# connector2.net
KiCad netlist of a schematic drawn in EAGLE
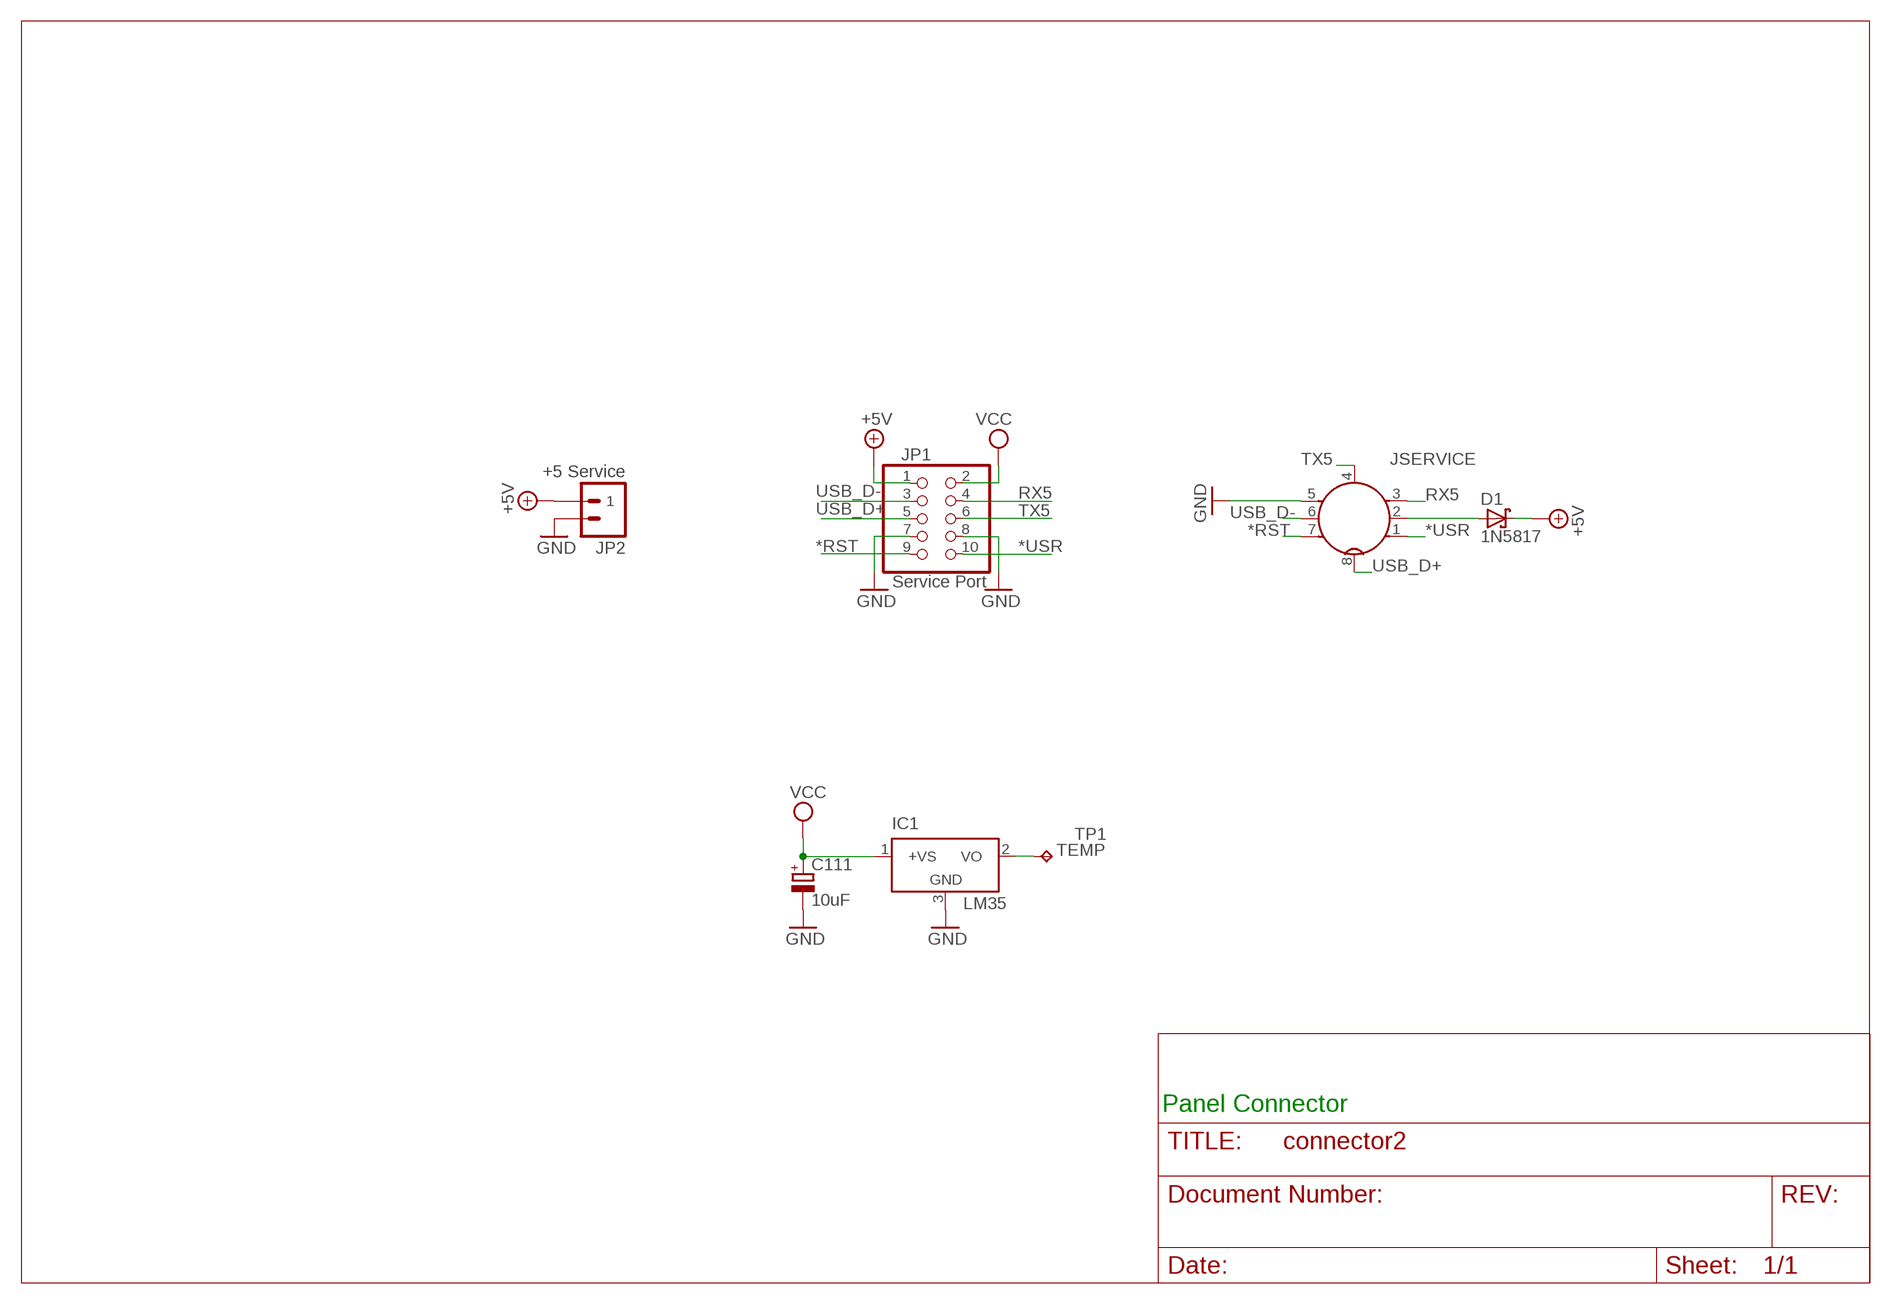
[diagram p0: schematic, sheet 1]

(export (version "E")
  (design (tool "Eeschema 10.0.6"))
  (components
    (comp (ref "C111")
      (value "10uF")
      (footprint "eagle-import:E2,5-6E")
      (libsource (lib "eagle-import") (part "CPOL-EUE2,5-6E"))
    )
    (comp (ref "D1")
      (value "1N5817")
      (footprint "eagle-import:DO41-150V")
      (libsource (lib "eagle-import") (part "1N5819-V"))
    )
    (comp (ref "IC1")
      (value "LM35")
      (footprint "eagle-import:TO92-50")
      (libsource (lib "eagle-import") (part "LM35"))
    )
    (comp (ref "JP1")
      (value "Service Port")
      (footprint "eagle-import:2X05")
      (libsource (lib "eagle-import") (part "HEADER-2X5"))
    )
    (comp (ref "JP2")
      (value "+5 Service")
      (footprint "eagle-import:MOLEX-1X2")
      (libsource (lib "eagle-import") (part "M02POLAR"))
    )
    (comp (ref "JSERVICE")
      (value "MIC_CONN_MALE_8P")
      (footprint "eagle-import:MIC_CONN_MALE_8P")
      (libsource (lib "eagle-import") (part "MIC_CONN_MALE_8P"))
    )
    (comp (ref "TP1")
      (value "TPPAD1-13")
      (footprint "eagle-import:P1-13")
      (fields (field (name "TP_SIGNAL_NAME") "TEMP"))
      (libsource (lib "eagle-import") (part "TPPAD1-13"))
    )
  )
  (nets
    (net (code "1") (name "+5V") (class "Default")
      (node (ref "D1") (pin "C") (pinfunction "C_C") (pintype "passive"))
      (node (ref "JP1") (pin "1") (pinfunction "1_1") (pintype "passive"))
      (node (ref "JP2") (pin "1") (pinfunction "1_1") (pintype "passive"))
    )
    (net (code "2") (name "/*RST") (class "Default")
      (node (ref "JP1") (pin "9") (pinfunction "9_9") (pintype "passive"))
      (node (ref "JSERVICE") (pin "7") (pinfunction "P7_7") (pintype "passive"))
    )
    (net (code "3") (name "/*USR") (class "Default")
      (node (ref "JP1") (pin "10") (pinfunction "10_10") (pintype "passive"))
      (node (ref "JSERVICE") (pin "1") (pinfunction "P1_1") (pintype "passive"))
    )
    (net (code "4") (name "/RX5") (class "Default")
      (node (ref "JP1") (pin "4") (pinfunction "4_4") (pintype "passive"))
      (node (ref "JSERVICE") (pin "3") (pinfunction "P3_3") (pintype "passive"))
    )
    (net (code "5") (name "/TX5") (class "Default")
      (node (ref "JP1") (pin "6") (pinfunction "6_6") (pintype "passive"))
      (node (ref "JSERVICE") (pin "4") (pinfunction "P4_4") (pintype "passive"))
    )
    (net (code "6") (name "/USB_D+") (class "Default")
      (node (ref "JP1") (pin "5") (pinfunction "5_5") (pintype "passive"))
      (node (ref "JSERVICE") (pin "8") (pinfunction "P8_8") (pintype "passive"))
    )
    (net (code "7") (name "/USB_D-") (class "Default")
      (node (ref "JP1") (pin "3") (pinfunction "3_3") (pintype "passive"))
      (node (ref "JSERVICE") (pin "6") (pinfunction "P6_6") (pintype "passive"))
    )
    (net (code "8") (name "GND") (class "Default")
      (node (ref "C111") (pin "-") (pinfunction "-_-") (pintype "passive"))
      (node (ref "IC1") (pin "3") (pinfunction "GND_3") (pintype "power_in"))
      (node (ref "JP1") (pin "7") (pinfunction "7_7") (pintype "passive"))
      (node (ref "JP1") (pin "8") (pinfunction "8_8") (pintype "passive"))
      (node (ref "JP2") (pin "2") (pinfunction "2_2") (pintype "passive"))
      (node (ref "JSERVICE") (pin "5") (pinfunction "P5_5") (pintype "passive"))
    )
    (net (code "9") (name "Net-(IC1-VO)") (class "Default")
      (node (ref "IC1") (pin "2") (pinfunction "VO_2") (pintype "output"))
      (node (ref "TP1") (pin "TP") (pinfunction "TP_TP") (pintype "input"))
    )
    (net (code "10") (name "Net-(JSERVICE-P2)") (class "Default")
      (node (ref "D1") (pin "A") (pinfunction "A_A") (pintype "passive"))
      (node (ref "JSERVICE") (pin "2") (pinfunction "P2_2") (pintype "passive"))
    )
    (net (code "11") (name "VCC") (class "Default")
      (node (ref "C111") (pin "+") (pinfunction "+_+") (pintype "passive"))
      (node (ref "IC1") (pin "1") (pinfunction "+VS_1") (pintype "input"))
      (node (ref "JP1") (pin "2") (pinfunction "2_2") (pintype "passive"))
    )
  )
)
